# IOB-Turtle.net
KiCad netlist of a schematic drawn in EAGLE
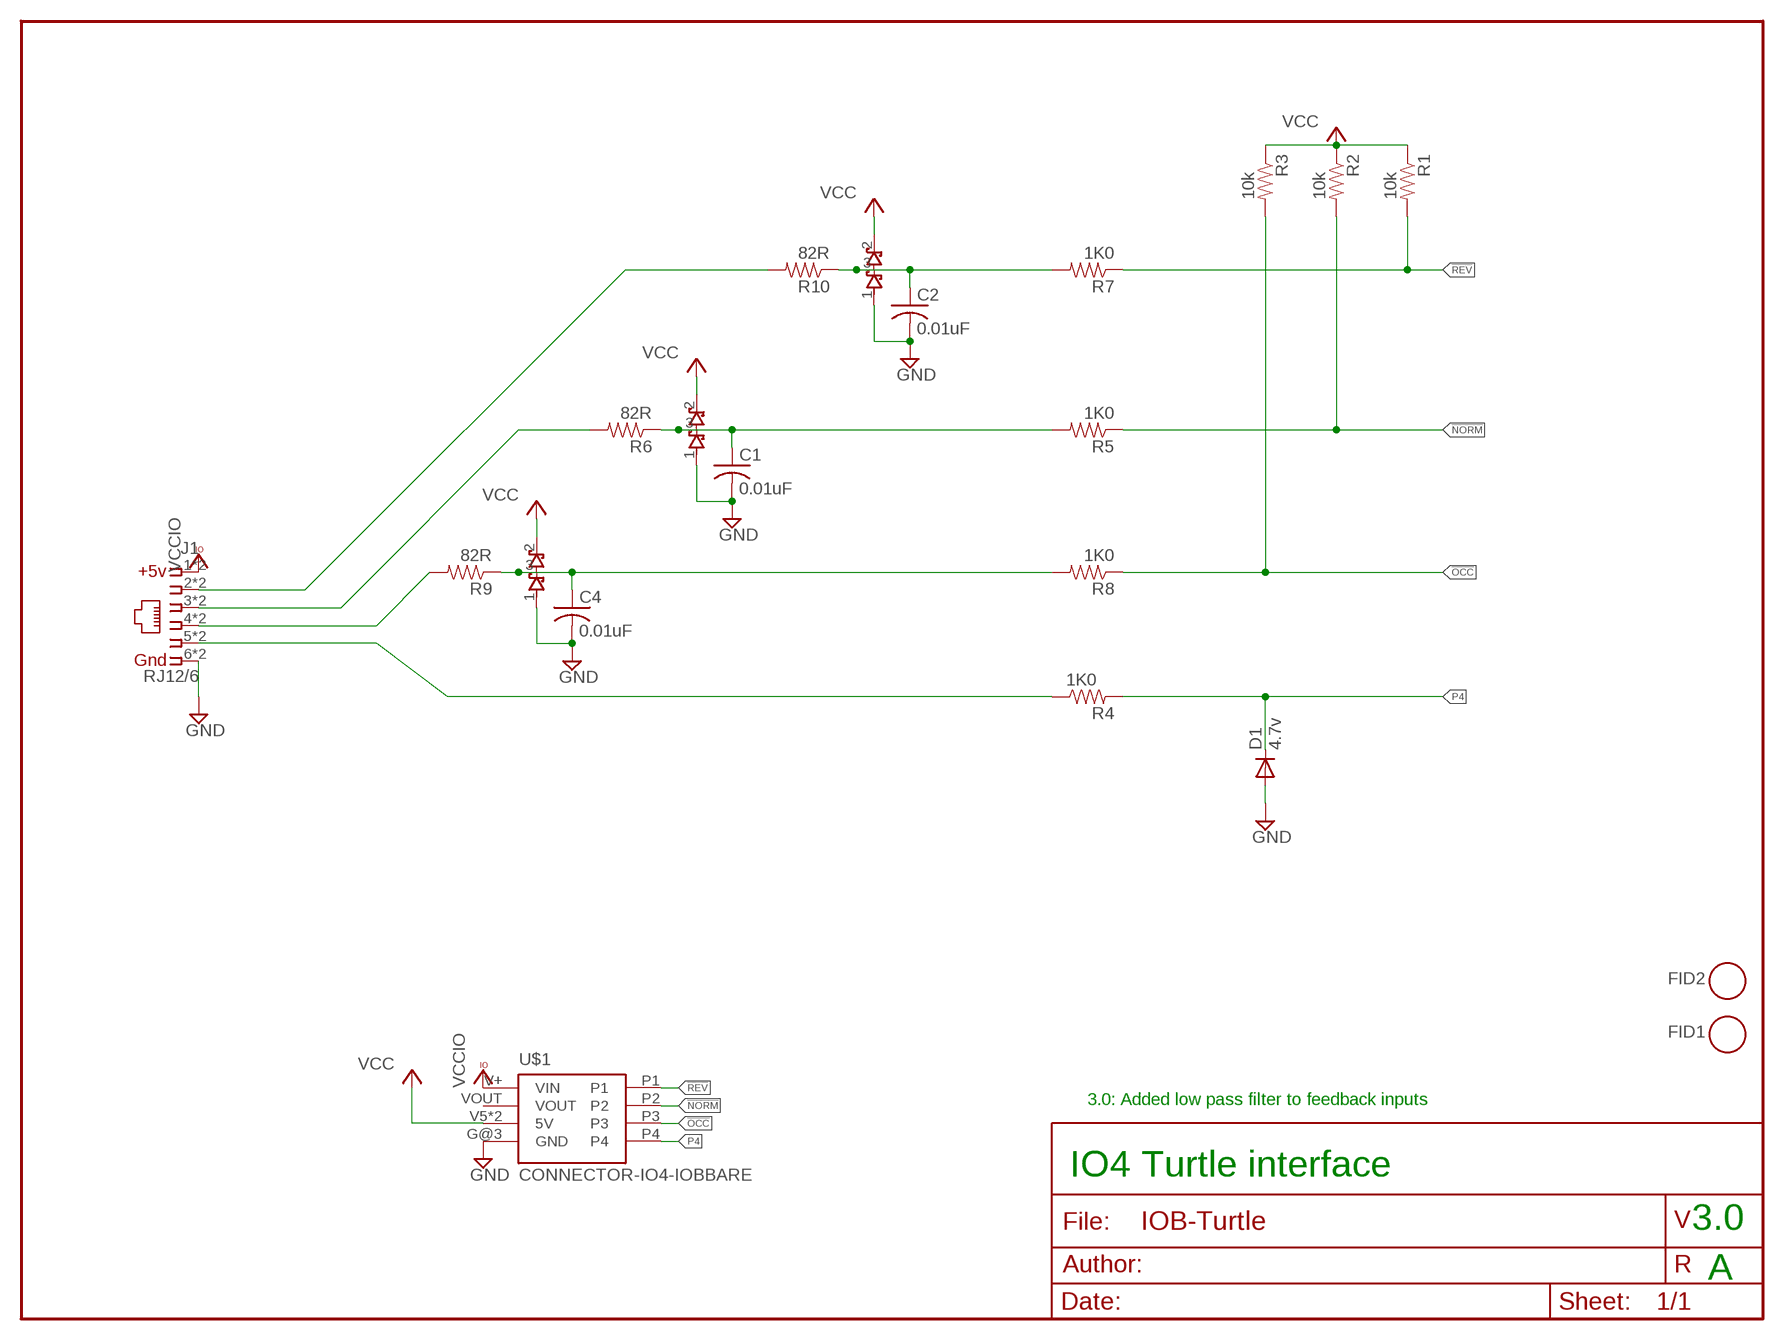
[diagram p0: schematic, sheet 1]

(export (version "E")
  (design (tool "Eeschema 10.0.6"))
  (components
    (comp (ref "C1")
      (value "0.01uF")
      (footprint "eagle-import:0603-CAP")
      (libsource (lib "eagle-import") (part "CAP0603"))
    )
    (comp (ref "C2")
      (value "0.01uF")
      (footprint "eagle-import:0603-CAP")
      (libsource (lib "eagle-import") (part "CAP0603"))
    )
    (comp (ref "C4")
      (value "0.01uF")
      (footprint "eagle-import:0603-CAP")
      (libsource (lib "eagle-import") (part "CAP0603"))
    )
    (comp (ref "D1")
      (value "4.7v")
      (footprint "eagle-import:SOT23-3")
      (libsource (lib "eagle-import") (part "DIODESOT23"))
    )
    (comp (ref "D2")
      (value "BAT54S")
      (footprint "eagle-import:SOT23")
      (libsource (lib "eagle-import") (part "DIODE-BAT54S23"))
    )
    (comp (ref "D3")
      (value "BAT54S")
      (footprint "eagle-import:SOT23")
      (libsource (lib "eagle-import") (part "DIODE-BAT54S23"))
    )
    (comp (ref "D4")
      (value "BAT54S")
      (footprint "eagle-import:SOT23")
      (libsource (lib "eagle-import") (part "DIODE-BAT54S23"))
    )
    (comp (ref "FID1")
      (value "FIDUCIAL")
      (footprint "eagle-import:FIDUCIAL_1MM")
      (libsource (lib "eagle-import") (part "FIDUCIAL"))
    )
    (comp (ref "FID2")
      (value "FIDUCIAL")
      (footprint "eagle-import:FIDUCIAL_1MM")
      (libsource (lib "eagle-import") (part "FIDUCIAL"))
    )
    (comp (ref "J1")
      (value "RJ12/6")
      (footprint "eagle-import:RJ24-INVERTED-PINS")
      (libsource (lib "eagle-import") (part "CONNECTOR-IO4IPINS"))
    )
    (comp (ref "R1")
      (value "10k")
      (footprint "eagle-import:0805-RES")
      (libsource (lib "eagle-import") (part "R0805-RES"))
    )
    (comp (ref "R2")
      (value "10k")
      (footprint "eagle-import:0805-RES")
      (libsource (lib "eagle-import") (part "R0805-RES"))
    )
    (comp (ref "R3")
      (value "10k")
      (footprint "eagle-import:0805-RES")
      (libsource (lib "eagle-import") (part "R0805-RES"))
    )
    (comp (ref "R4")
      (value "1K0")
      (footprint "eagle-import:0603-RES")
      (libsource (lib "eagle-import") (part "R0603-RES"))
    )
    (comp (ref "R5")
      (value "1K0")
      (footprint "eagle-import:0603-RES")
      (libsource (lib "eagle-import") (part "R0603-RES"))
    )
    (comp (ref "R6")
      (value "82R")
      (footprint "eagle-import:0805-RES")
      (libsource (lib "eagle-import") (part "R0805-RES"))
    )
    (comp (ref "R7")
      (value "1K0")
      (footprint "eagle-import:0603-RES")
      (libsource (lib "eagle-import") (part "R0603-RES"))
    )
    (comp (ref "R8")
      (value "1K0")
      (footprint "eagle-import:0603-RES")
      (libsource (lib "eagle-import") (part "R0603-RES"))
    )
    (comp (ref "R9")
      (value "82R")
      (footprint "eagle-import:0805-RES")
      (libsource (lib "eagle-import") (part "R0805-RES"))
    )
    (comp (ref "R10")
      (value "82R")
      (footprint "eagle-import:0805-RES")
      (libsource (lib "eagle-import") (part "R0805-RES"))
    )
    (comp (ref "U$1")
      (value "CONNECTOR-IO4-IOBBARE")
      (footprint "eagle-import:IO4-IOB")
      (libsource (lib "eagle-import") (part "CONNECTOR-IO4-IOBBARE"))
    )
  )
  (nets
    (net (code "1") (name "/VOUT") (class "Default")
      (node (ref "U$1") (pin "VOUT") (pinfunction "VOUT_VOUT") (pintype "power_in"))
    )
    (net (code "2") (name "/~{NORM}") (class "Default")
      (node (ref "R2") (pin "2") (pinfunction "2_2") (pintype "passive"))
      (node (ref "R5") (pin "1") (pinfunction "1_1") (pintype "passive"))
      (node (ref "U$1") (pin "P2") (pinfunction "P2_P2") (pintype "bidirectional"))
    )
    (net (code "3") (name "/~{OCC}") (class "Default")
      (node (ref "R3") (pin "2") (pinfunction "2_2") (pintype "passive"))
      (node (ref "R8") (pin "1") (pinfunction "1_1") (pintype "passive"))
      (node (ref "U$1") (pin "P3") (pinfunction "P3_P3") (pintype "bidirectional"))
    )
    (net (code "4") (name "/~{REV}") (class "Default")
      (node (ref "R1") (pin "2") (pinfunction "2_2") (pintype "passive"))
      (node (ref "R7") (pin "1") (pinfunction "1_1") (pintype "passive"))
      (node (ref "U$1") (pin "P1") (pinfunction "P1_P1") (pintype "bidirectional"))
    )
    (net (code "5") (name "GND") (class "Default")
      (node (ref "C1") (pin "2") (pinfunction "2_2") (pintype "passive"))
      (node (ref "C2") (pin "2") (pinfunction "2_2") (pintype "passive"))
      (node (ref "C4") (pin "2") (pinfunction "2_2") (pintype "passive"))
      (node (ref "D1") (pin "1") (pinfunction "A_1") (pintype "passive"))
      (node (ref "D2") (pin "1") (pinfunction "A1_1") (pintype "bidirectional"))
      (node (ref "D3") (pin "1") (pinfunction "A1_1") (pintype "bidirectional"))
      (node (ref "D4") (pin "1") (pinfunction "A1_1") (pintype "bidirectional"))
      (node (ref "J1") (pin "6") (pinfunction "6_6") (pintype "power_in"))
      (node (ref "J1") (pin "6@1") (pinfunction "6_6@1") (pintype "power_in"))
      (node (ref "U$1") (pin "G@3") (pinfunction "GND_G@3") (pintype "power_in"))
    )
    (net (code "6") (name "Net-(D2-COM)") (class "Default")
      (node (ref "C1") (pin "1") (pinfunction "1_1") (pintype "passive"))
      (node (ref "D2") (pin "3") (pinfunction "COM_3") (pintype "bidirectional"))
      (node (ref "R5") (pin "2") (pinfunction "2_2") (pintype "passive"))
      (node (ref "R6") (pin "1") (pinfunction "1_1") (pintype "passive"))
    )
    (net (code "7") (name "Net-(D3-COM)") (class "Default")
      (node (ref "C2") (pin "1") (pinfunction "1_1") (pintype "passive"))
      (node (ref "D3") (pin "3") (pinfunction "COM_3") (pintype "bidirectional"))
      (node (ref "R10") (pin "1") (pinfunction "1_1") (pintype "passive"))
      (node (ref "R7") (pin "2") (pinfunction "2_2") (pintype "passive"))
    )
    (net (code "8") (name "Net-(D4-COM)") (class "Default")
      (node (ref "C4") (pin "1") (pinfunction "1_1") (pintype "passive"))
      (node (ref "D4") (pin "3") (pinfunction "COM_3") (pintype "bidirectional"))
      (node (ref "R8") (pin "2") (pinfunction "2_2") (pintype "passive"))
      (node (ref "R9") (pin "1") (pinfunction "1_1") (pintype "passive"))
    )
    (net (code "9") (name "Net-(J1-2-Pad2@1)") (class "Default")
      (node (ref "J1") (pin "2") (pinfunction "2_2") (pintype "passive"))
      (node (ref "J1") (pin "2@1") (pinfunction "2_2@1") (pintype "passive"))
      (node (ref "R10") (pin "2") (pinfunction "2_2") (pintype "passive"))
    )
    (net (code "10") (name "Net-(J1-3-Pad3@1)") (class "Default")
      (node (ref "J1") (pin "3") (pinfunction "3_3") (pintype "passive"))
      (node (ref "J1") (pin "3@1") (pinfunction "3_3@1") (pintype "passive"))
      (node (ref "R6") (pin "2") (pinfunction "2_2") (pintype "passive"))
    )
    (net (code "11") (name "Net-(J1-4-Pad4@1)") (class "Default")
      (node (ref "J1") (pin "4") (pinfunction "4_4") (pintype "passive"))
      (node (ref "J1") (pin "4@1") (pinfunction "4_4@1") (pintype "passive"))
      (node (ref "R9") (pin "2") (pinfunction "2_2") (pintype "passive"))
    )
    (net (code "12") (name "Net-(J1-5-Pad5@1)") (class "Default")
      (node (ref "J1") (pin "5") (pinfunction "5_5") (pintype "passive"))
      (node (ref "J1") (pin "5@1") (pinfunction "5_5@1") (pintype "passive"))
      (node (ref "R4") (pin "1") (pinfunction "1_1") (pintype "passive"))
    )
    (net (code "13") (name "P4") (class "Default")
      (node (ref "D1") (pin "3") (pinfunction "C_3") (pintype "passive"))
      (node (ref "R4") (pin "2") (pinfunction "2_2") (pintype "passive"))
      (node (ref "U$1") (pin "P4") (pinfunction "P4_P4") (pintype "bidirectional"))
    )
    (net (code "14") (name "VCC") (class "Default")
      (node (ref "D2") (pin "2") (pinfunction "C2_2") (pintype "bidirectional"))
      (node (ref "D3") (pin "2") (pinfunction "C2_2") (pintype "bidirectional"))
      (node (ref "D4") (pin "2") (pinfunction "C2_2") (pintype "bidirectional"))
      (node (ref "R1") (pin "1") (pinfunction "1_1") (pintype "passive"))
      (node (ref "R2") (pin "1") (pinfunction "1_1") (pintype "passive"))
      (node (ref "R3") (pin "1") (pinfunction "1_1") (pintype "passive"))
      (node (ref "U$1") (pin "V5") (pinfunction "5V_V5") (pintype "power_in"))
      (node (ref "U$1") (pin "V5@1") (pinfunction "5V_V5@1") (pintype "power_in"))
    )
    (net (code "15") (name "VCCIO") (class "Default")
      (node (ref "J1") (pin "1") (pinfunction "1_1") (pintype "power_in"))
      (node (ref "J1") (pin "1@1") (pinfunction "1_1@1") (pintype "power_in"))
      (node (ref "U$1") (pin "V+") (pinfunction "VIN_V+") (pintype "power_in"))
    )
  )
)
